# DRAMCarrier_250466.net
KiCad netlist of a schematic drawn in EAGLE
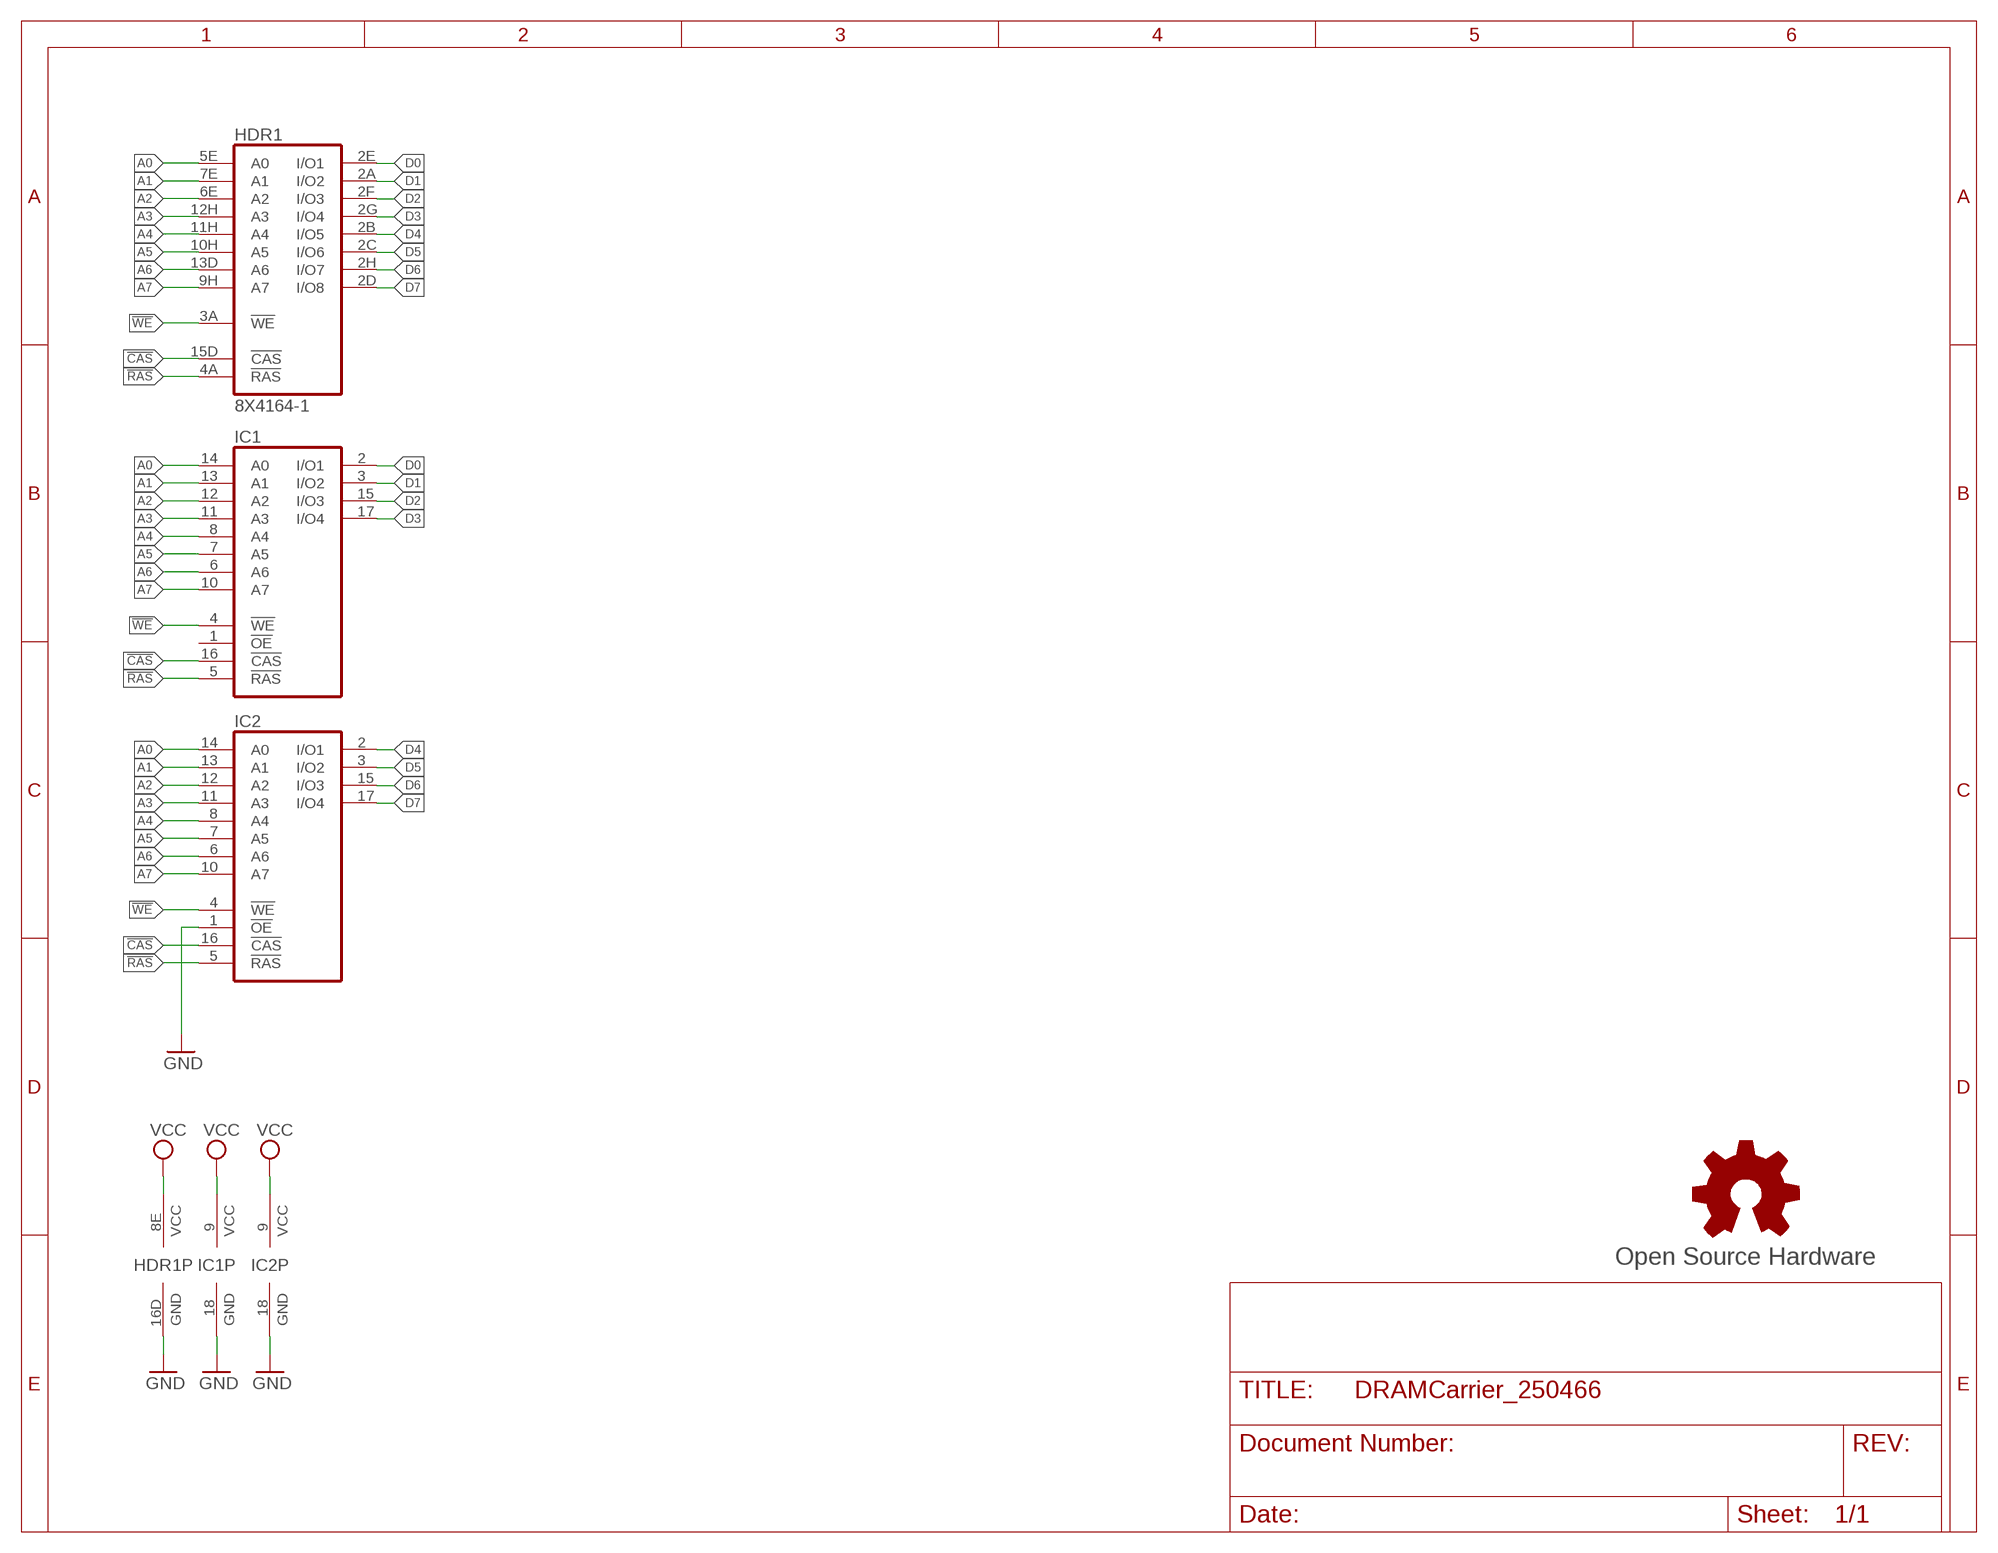
[diagram p0: schematic, sheet 1]

(export (version "E")
  (design (tool "Eeschema 10.0.6"))
  (components
    (comp (ref "GOLD_ORB_SM1")
      (value "Open Source Hardware")
      (footprint "eagle-import:OSHW_8MM")
      (libsource (lib "eagle-import") (part "OSHWLOGOLOGO8MM"))
    )
    (comp (ref "HDR1")
      (value "8X4164-1")
      (footprint "eagle-import:8XDIL16_REV")
      (libsource (lib "eagle-import") (part "8X4164-1"))
    )
    (comp (ref "IC1")
      (value "41464C")
      (footprint "eagle-import:DIL18")
      (libsource (lib "eagle-import") (part "41464C"))
    )
    (comp (ref "IC2")
      (value "41464C")
      (footprint "eagle-import:DIL18")
      (libsource (lib "eagle-import") (part "41464C"))
    )
  )
  (nets
    (net (code "1") (name "/~{CAS}") (class "Default")
      (node (ref "HDR1") (pin "15D") (pinfunction "~{CAS}_15D") (pintype "input"))
      (node (ref "IC1") (pin "16") (pinfunction "~{CAS}_16") (pintype "input"))
      (node (ref "IC2") (pin "16") (pinfunction "~{CAS}_16") (pintype "input"))
    )
    (net (code "2") (name "/~{RAS}") (class "Default")
      (node (ref "HDR1") (pin "4A") (pinfunction "~{RAS}_4A") (pintype "input"))
      (node (ref "IC1") (pin "5") (pinfunction "~{RAS}_5") (pintype "input"))
      (node (ref "IC2") (pin "5") (pinfunction "~{RAS}_5") (pintype "input"))
    )
    (net (code "3") (name "/~{WE}") (class "Default")
      (node (ref "HDR1") (pin "3A") (pinfunction "~{WE}_3A") (pintype "input"))
      (node (ref "IC1") (pin "4") (pinfunction "~{WE}_4") (pintype "input"))
      (node (ref "IC2") (pin "4") (pinfunction "~{WE}_4") (pintype "input"))
    )
    (net (code "4") (name "A0") (class "Default")
      (node (ref "HDR1") (pin "5E") (pinfunction "A0_5E") (pintype "input"))
      (node (ref "IC1") (pin "14") (pinfunction "A0_14") (pintype "input"))
      (node (ref "IC2") (pin "14") (pinfunction "A0_14") (pintype "input"))
    )
    (net (code "5") (name "A1") (class "Default")
      (node (ref "HDR1") (pin "7E") (pinfunction "A1_7E") (pintype "input"))
      (node (ref "IC1") (pin "13") (pinfunction "A1_13") (pintype "input"))
      (node (ref "IC2") (pin "13") (pinfunction "A1_13") (pintype "input"))
    )
    (net (code "6") (name "A2") (class "Default")
      (node (ref "HDR1") (pin "6E") (pinfunction "A2_6E") (pintype "input"))
      (node (ref "IC1") (pin "12") (pinfunction "A2_12") (pintype "input"))
      (node (ref "IC2") (pin "12") (pinfunction "A2_12") (pintype "input"))
    )
    (net (code "7") (name "A3") (class "Default")
      (node (ref "HDR1") (pin "12H") (pinfunction "A3_12H") (pintype "input"))
      (node (ref "IC1") (pin "11") (pinfunction "A3_11") (pintype "input"))
      (node (ref "IC2") (pin "11") (pinfunction "A3_11") (pintype "input"))
    )
    (net (code "8") (name "A4") (class "Default")
      (node (ref "HDR1") (pin "11H") (pinfunction "A4_11H") (pintype "input"))
      (node (ref "IC1") (pin "8") (pinfunction "A4_8") (pintype "input"))
      (node (ref "IC2") (pin "8") (pinfunction "A4_8") (pintype "input"))
    )
    (net (code "9") (name "A5") (class "Default")
      (node (ref "HDR1") (pin "10H") (pinfunction "A5_10H") (pintype "input"))
      (node (ref "IC1") (pin "7") (pinfunction "A5_7") (pintype "input"))
      (node (ref "IC2") (pin "7") (pinfunction "A5_7") (pintype "input"))
    )
    (net (code "10") (name "A6") (class "Default")
      (node (ref "HDR1") (pin "13D") (pinfunction "A6_13D") (pintype "input"))
      (node (ref "IC1") (pin "6") (pinfunction "A6_6") (pintype "input"))
      (node (ref "IC2") (pin "6") (pinfunction "A6_6") (pintype "input"))
    )
    (net (code "11") (name "A7") (class "Default")
      (node (ref "HDR1") (pin "9H") (pinfunction "A7_9H") (pintype "input"))
      (node (ref "IC1") (pin "10") (pinfunction "A7_10") (pintype "input"))
      (node (ref "IC2") (pin "10") (pinfunction "A7_10") (pintype "input"))
    )
    (net (code "12") (name "D0") (class "Default")
      (node (ref "HDR1") (pin "2E") (pinfunction "I/O1_2E") (pintype "bidirectional"))
      (node (ref "IC1") (pin "2") (pinfunction "I/O1_2") (pintype "bidirectional"))
    )
    (net (code "13") (name "D1") (class "Default")
      (node (ref "HDR1") (pin "2A") (pinfunction "I/O2_2A") (pintype "bidirectional"))
      (node (ref "IC1") (pin "3") (pinfunction "I/O2_3") (pintype "bidirectional"))
    )
    (net (code "14") (name "D2") (class "Default")
      (node (ref "HDR1") (pin "2F") (pinfunction "I/O3_2F") (pintype "bidirectional"))
      (node (ref "IC1") (pin "15") (pinfunction "I/O3_15") (pintype "bidirectional"))
    )
    (net (code "15") (name "D3") (class "Default")
      (node (ref "HDR1") (pin "2G") (pinfunction "I/O4_2G") (pintype "bidirectional"))
      (node (ref "IC1") (pin "17") (pinfunction "I/O4_17") (pintype "bidirectional"))
    )
    (net (code "16") (name "D4") (class "Default")
      (node (ref "HDR1") (pin "2B") (pinfunction "I/O5_2B") (pintype "bidirectional"))
      (node (ref "IC2") (pin "2") (pinfunction "I/O1_2") (pintype "bidirectional"))
    )
    (net (code "17") (name "D5") (class "Default")
      (node (ref "HDR1") (pin "2C") (pinfunction "I/O6_2C") (pintype "bidirectional"))
      (node (ref "IC2") (pin "3") (pinfunction "I/O2_3") (pintype "bidirectional"))
    )
    (net (code "18") (name "D6") (class "Default")
      (node (ref "HDR1") (pin "2H") (pinfunction "I/O7_2H") (pintype "bidirectional"))
      (node (ref "IC2") (pin "15") (pinfunction "I/O3_15") (pintype "bidirectional"))
    )
    (net (code "19") (name "D7") (class "Default")
      (node (ref "HDR1") (pin "2D") (pinfunction "I/O8_2D") (pintype "bidirectional"))
      (node (ref "IC2") (pin "17") (pinfunction "I/O4_17") (pintype "bidirectional"))
    )
    (net (code "20") (name "GND") (class "Default")
      (node (ref "HDR1") (pin "16D") (pinfunction "GND_16D") (pintype "power_in"))
      (node (ref "IC1") (pin "18") (pinfunction "GND_18") (pintype "power_in"))
      (node (ref "IC2") (pin "1") (pinfunction "~{OE}_1") (pintype "input"))
      (node (ref "IC2") (pin "18") (pinfunction "GND_18") (pintype "power_in"))
    )
    (net (code "21") (name "VCC") (class "Default")
      (node (ref "HDR1") (pin "8E") (pinfunction "VCC_8E") (pintype "power_in"))
      (node (ref "IC1") (pin "9") (pinfunction "VCC_9") (pintype "power_in"))
      (node (ref "IC2") (pin "9") (pinfunction "VCC_9") (pintype "power_in"))
    )
    (net (code "22") (name "unconnected-(IC1A-~{OE}-Pad1)") (class "Default")
      (node (ref "IC1") (pin "1") (pinfunction "~{OE}_1") (pintype "input"))
    )
  )
)
